# Adafruit_2_7in_Sharp_Memory_Display.net
KiCad netlist of a schematic drawn in EAGLE
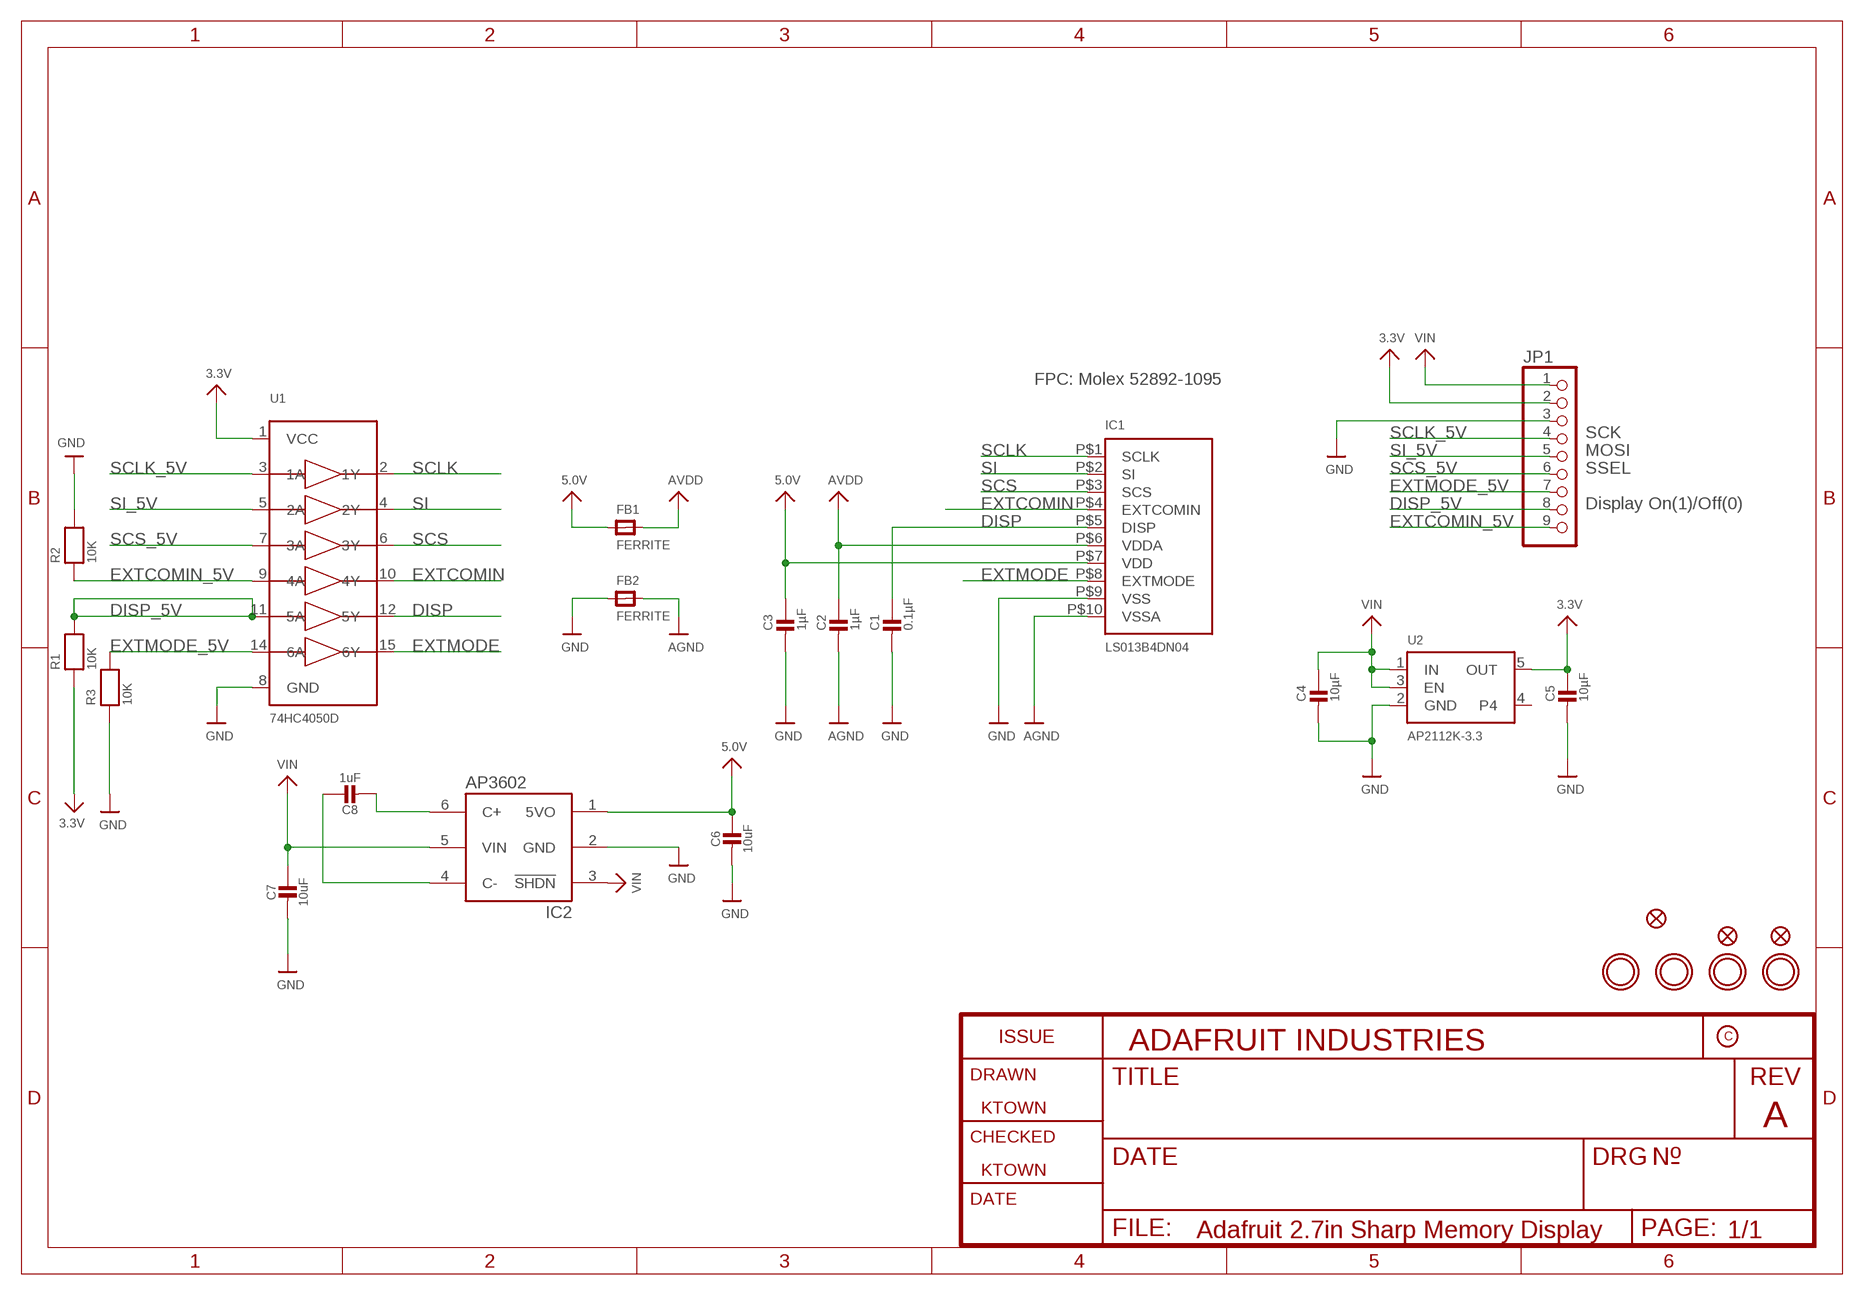
[diagram p0: schematic, sheet 1]

(export (version "E")
  (design (tool "Eeschema 10.0.6"))
  (components
    (comp (ref "C1")
      (value "0.1µF")
      (footprint "eagle-import:0603-NO")
      (libsource (lib "eagle-import") (part "CAP_CERAMIC0603_NO"))
    )
    (comp (ref "C2")
      (value "1µF")
      (footprint "eagle-import:0805_10MGAP")
      (libsource (lib "eagle-import") (part "CAP_CERAMIC0805_10MGAP"))
    )
    (comp (ref "C3")
      (value "1µF")
      (footprint "eagle-import:0805-NO")
      (libsource (lib "eagle-import") (part "CAP_CERAMIC0805-NOOUTLINE"))
    )
    (comp (ref "C4")
      (value "10µF")
      (footprint "eagle-import:0805-NO")
      (fields (field (name "REV") "A"))
      (libsource (lib "eagle-import") (part "CAP_CERAMIC0805-NOOUTLINE"))
    )
    (comp (ref "C5")
      (value "10µF")
      (footprint "eagle-import:0805-NO")
      (fields (field (name "REV") "A"))
      (libsource (lib "eagle-import") (part "CAP_CERAMIC0805-NOOUTLINE"))
    )
    (comp (ref "C6")
      (value "10uF")
      (footprint "eagle-import:0805-NO")
      (libsource (lib "eagle-import") (part "CAP_CERAMIC0805-NOOUTLINE"))
    )
    (comp (ref "C7")
      (value "10uF")
      (footprint "eagle-import:0805-NO")
      (libsource (lib "eagle-import") (part "CAP_CERAMIC0805-NOOUTLINE"))
    )
    (comp (ref "C8")
      (value "1uF")
      (footprint "eagle-import:0805-NO")
      (libsource (lib "eagle-import") (part "CAP_CERAMIC0805-NOOUTLINE"))
    )
    (comp (ref "FB1")
      (value "FERRITE")
      (footprint "eagle-import:_0805")
      (libsource (lib "eagle-import") (part "FERRITE_0805"))
    )
    (comp (ref "FB2")
      (value "FERRITE")
      (footprint "eagle-import:_0805")
      (libsource (lib "eagle-import") (part "FERRITE_0805"))
    )
    (comp (ref "FID1")
      (value "FIDUCIAL_1MM")
      (footprint "eagle-import:FIDUCIAL_1MM")
      (libsource (lib "eagle-import") (part "FIDUCIAL_1MM"))
    )
    (comp (ref "FID2")
      (value "FIDUCIAL_1MM")
      (footprint "eagle-import:FIDUCIAL_1MM")
      (libsource (lib "eagle-import") (part "FIDUCIAL_1MM"))
    )
    (comp (ref "FID3")
      (value "FIDUCIAL_1MM")
      (footprint "eagle-import:FIDUCIAL_1MM")
      (fields (field (name "REV") "A"))
      (libsource (lib "eagle-import") (part "FIDUCIAL_1MM"))
    )
    (comp (ref "IC1")
      (value "LS013B4DN04")
      (footprint "eagle-import:SHARP_2.7IN")
      (libsource (lib "eagle-import") (part "DISP_EINK_SHARPMEMORYLCD_10PIN_27IN"))
    )
    (comp (ref "IC2")
      (value "AP3602")
      (footprint "eagle-import:SOT23-6")
      (libsource (lib "eagle-import") (part "AP3602"))
    )
    (comp (ref "JP1")
      (value "HEADER-1X970MIL")
      (footprint "eagle-import:1X09_ROUND_70")
      (libsource (lib "eagle-import") (part "HEADER-1X970MIL"))
    )
    (comp (ref "R1")
      (value "10K")
      (footprint "eagle-import:0603-NO")
      (libsource (lib "eagle-import") (part "RESISTOR_0603_NOOUT"))
    )
    (comp (ref "R2")
      (value "10K")
      (footprint "eagle-import:0603-NO")
      (libsource (lib "eagle-import") (part "RESISTOR_0603_NOOUT"))
    )
    (comp (ref "R3")
      (value "10K")
      (footprint "eagle-import:0603-NO")
      (fields (field (name "REV") "A"))
      (libsource (lib "eagle-import") (part "RESISTOR_0603_NOOUT"))
    )
    (comp (ref "U$21")
      (value "MOUNTINGHOLE2.5_THICK")
      (footprint "eagle-import:MOUNTINGHOLE_2.5_PLATED_THICK")
      (libsource (lib "eagle-import") (part "MOUNTINGHOLE2.5_THICK"))
    )
    (comp (ref "U$22")
      (value "MOUNTINGHOLE2.5_THICK")
      (footprint "eagle-import:MOUNTINGHOLE_2.5_PLATED_THICK")
      (libsource (lib "eagle-import") (part "MOUNTINGHOLE2.5_THICK"))
    )
    (comp (ref "U$27")
      (value "MOUNTINGHOLE2.5")
      (footprint "eagle-import:MOUNTINGHOLE_2.5_PLATED")
      (fields (field (name "REV") "A"))
      (libsource (lib "eagle-import") (part "MOUNTINGHOLE2.5"))
    )
    (comp (ref "U$28")
      (value "MOUNTINGHOLE2.5")
      (footprint "eagle-import:MOUNTINGHOLE_2.5_PLATED")
      (fields (field (name "REV") "A"))
      (libsource (lib "eagle-import") (part "MOUNTINGHOLE2.5"))
    )
    (comp (ref "U1")
      (value "74HC4050D")
      (footprint "eagle-import:SOIC16")
      (libsource (lib "eagle-import") (part "74HC4050D"))
    )
    (comp (ref "U2")
      (value "AP2112K-3.3")
      (footprint "eagle-import:SOT23-5")
      (libsource (lib "eagle-import") (part "VREG_SOT23-5"))
    )
  )
  (nets
    (net (code "1") (name "/DISP") (class "Default")
      (node (ref "C1") (pin "1") (pinfunction "1_1") (pintype "passive"))
      (node (ref "IC1") (pin "P$5") (pinfunction "DISP_P$5") (pintype "input"))
      (node (ref "U1") (pin "12") (pinfunction "5Y_12") (pintype "bidirectional"))
    )
    (net (code "2") (name "/DISP_5V") (class "Default")
      (node (ref "JP1") (pin "8") (pinfunction "8_8") (pintype "passive"))
      (node (ref "R1") (pin "2") (pinfunction "2_2") (pintype "passive"))
      (node (ref "U1") (pin "11") (pinfunction "5A_11") (pintype "bidirectional"))
    )
    (net (code "3") (name "/EXTCOMIN") (class "Default")
      (node (ref "IC1") (pin "P$4") (pinfunction "EXTCOMIN_P$4") (pintype "input"))
      (node (ref "U1") (pin "10") (pinfunction "4Y_10") (pintype "bidirectional"))
    )
    (net (code "4") (name "/EXTCOMIN_5V") (class "Default")
      (node (ref "JP1") (pin "9") (pinfunction "9_9") (pintype "passive"))
      (node (ref "R2") (pin "1") (pinfunction "1_1") (pintype "passive"))
      (node (ref "U1") (pin "9") (pinfunction "4A_9") (pintype "bidirectional"))
    )
    (net (code "5") (name "/EXTMODE") (class "Default")
      (node (ref "IC1") (pin "P$8") (pinfunction "EXTMODE_P$8") (pintype "input"))
      (node (ref "U1") (pin "15") (pinfunction "6Y_15") (pintype "bidirectional"))
    )
    (net (code "6") (name "/EXTMODE_5V") (class "Default")
      (node (ref "JP1") (pin "7") (pinfunction "7_7") (pintype "passive"))
      (node (ref "R3") (pin "2") (pinfunction "2_2") (pintype "passive"))
      (node (ref "U1") (pin "14") (pinfunction "6A_14") (pintype "bidirectional"))
    )
    (net (code "7") (name "/SCLK") (class "Default")
      (node (ref "IC1") (pin "P$1") (pinfunction "SCLK_P$1") (pintype "input"))
      (node (ref "U1") (pin "2") (pinfunction "1Y_2") (pintype "bidirectional"))
    )
    (net (code "8") (name "/SCLK_5V") (class "Default")
      (node (ref "JP1") (pin "4") (pinfunction "4_4") (pintype "passive"))
      (node (ref "U1") (pin "3") (pinfunction "1A_3") (pintype "bidirectional"))
    )
    (net (code "9") (name "/SCS") (class "Default")
      (node (ref "IC1") (pin "P$3") (pinfunction "SCS_P$3") (pintype "input"))
      (node (ref "U1") (pin "6") (pinfunction "3Y_6") (pintype "bidirectional"))
    )
    (net (code "10") (name "/SCS_5V") (class "Default")
      (node (ref "JP1") (pin "6") (pinfunction "6_6") (pintype "passive"))
      (node (ref "U1") (pin "7") (pinfunction "3A_7") (pintype "bidirectional"))
    )
    (net (code "11") (name "/SI") (class "Default")
      (node (ref "IC1") (pin "P$2") (pinfunction "SI_P$2") (pintype "input"))
      (node (ref "U1") (pin "4") (pinfunction "2Y_4") (pintype "bidirectional"))
    )
    (net (code "12") (name "/SI_5V") (class "Default")
      (node (ref "JP1") (pin "5") (pinfunction "5_5") (pintype "passive"))
      (node (ref "U1") (pin "5") (pinfunction "2A_5") (pintype "bidirectional"))
    )
    (net (code "13") (name "3.3V") (class "Default")
      (node (ref "C5") (pin "1") (pinfunction "1_1") (pintype "passive"))
      (node (ref "JP1") (pin "2") (pinfunction "2_2") (pintype "passive"))
      (node (ref "R1") (pin "1") (pinfunction "1_1") (pintype "passive"))
      (node (ref "U1") (pin "1") (pinfunction "VCC_1") (pintype "bidirectional"))
      (node (ref "U2") (pin "5") (pinfunction "OUT_5") (pintype "power_in"))
    )
    (net (code "14") (name "5.0V") (class "Default")
      (node (ref "C3") (pin "1") (pinfunction "1_1") (pintype "passive"))
      (node (ref "C6") (pin "1") (pinfunction "1_1") (pintype "passive"))
      (node (ref "FB1") (pin "1") (pinfunction "P$1_1") (pintype "passive"))
      (node (ref "IC1") (pin "P$7") (pinfunction "VDD_P$7") (pintype "power_in"))
      (node (ref "IC2") (pin "1") (pinfunction "5VO_1") (pintype "power_in"))
    )
    (net (code "15") (name "AGND") (class "Default")
      (node (ref "C2") (pin "2") (pinfunction "2_2") (pintype "passive"))
      (node (ref "FB2") (pin "2") (pinfunction "P$2_2") (pintype "passive"))
      (node (ref "IC1") (pin "P$10") (pinfunction "VSSA_P$10") (pintype "power_in"))
    )
    (net (code "16") (name "AVDD") (class "Default")
      (node (ref "C2") (pin "1") (pinfunction "1_1") (pintype "passive"))
      (node (ref "FB1") (pin "2") (pinfunction "P$2_2") (pintype "passive"))
      (node (ref "IC1") (pin "P$6") (pinfunction "VDDA_P$6") (pintype "power_in"))
    )
    (net (code "17") (name "GND") (class "Default")
      (node (ref "C1") (pin "2") (pinfunction "2_2") (pintype "passive"))
      (node (ref "C3") (pin "2") (pinfunction "2_2") (pintype "passive"))
      (node (ref "C4") (pin "2") (pinfunction "2_2") (pintype "passive"))
      (node (ref "C5") (pin "2") (pinfunction "2_2") (pintype "passive"))
      (node (ref "C6") (pin "2") (pinfunction "2_2") (pintype "passive"))
      (node (ref "C7") (pin "2") (pinfunction "2_2") (pintype "passive"))
      (node (ref "FB2") (pin "1") (pinfunction "P$1_1") (pintype "passive"))
      (node (ref "IC1") (pin "P$9") (pinfunction "VSS_P$9") (pintype "power_in"))
      (node (ref "IC2") (pin "2") (pinfunction "GND_2") (pintype "power_in"))
      (node (ref "JP1") (pin "3") (pinfunction "3_3") (pintype "passive"))
      (node (ref "R2") (pin "2") (pinfunction "2_2") (pintype "passive"))
      (node (ref "R3") (pin "1") (pinfunction "1_1") (pintype "passive"))
      (node (ref "U1") (pin "8") (pinfunction "GND_8") (pintype "bidirectional"))
      (node (ref "U2") (pin "2") (pinfunction "GND_2") (pintype "power_in"))
    )
    (net (code "18") (name "Net-(IC2-C+)") (class "Default")
      (node (ref "C8") (pin "2") (pinfunction "2_2") (pintype "passive"))
      (node (ref "IC2") (pin "6") (pinfunction "C+_6") (pintype "bidirectional"))
    )
    (net (code "19") (name "Net-(IC2-C-)") (class "Default")
      (node (ref "C8") (pin "1") (pinfunction "1_1") (pintype "passive"))
      (node (ref "IC2") (pin "4") (pinfunction "C-_4") (pintype "bidirectional"))
    )
    (net (code "20") (name "VIN") (class "Default")
      (node (ref "C4") (pin "1") (pinfunction "1_1") (pintype "passive"))
      (node (ref "C7") (pin "1") (pinfunction "1_1") (pintype "passive"))
      (node (ref "IC2") (pin "3") (pinfunction "~{SHDN}_3") (pintype "input"))
      (node (ref "IC2") (pin "5") (pinfunction "VIN_5") (pintype "power_in"))
      (node (ref "JP1") (pin "1") (pinfunction "1_1") (pintype "passive"))
      (node (ref "U2") (pin "1") (pinfunction "IN_1") (pintype "power_in"))
      (node (ref "U2") (pin "3") (pinfunction "EN_3") (pintype "input"))
    )
    (net (code "21") (name "unconnected-(U2-P4-Pad4)") (class "Default")
      (node (ref "U2") (pin "4") (pinfunction "P4_4") (pintype "bidirectional"))
    )
  )
)
